# Swig2.net
KiCad netlist of a schematic drawn in EAGLE
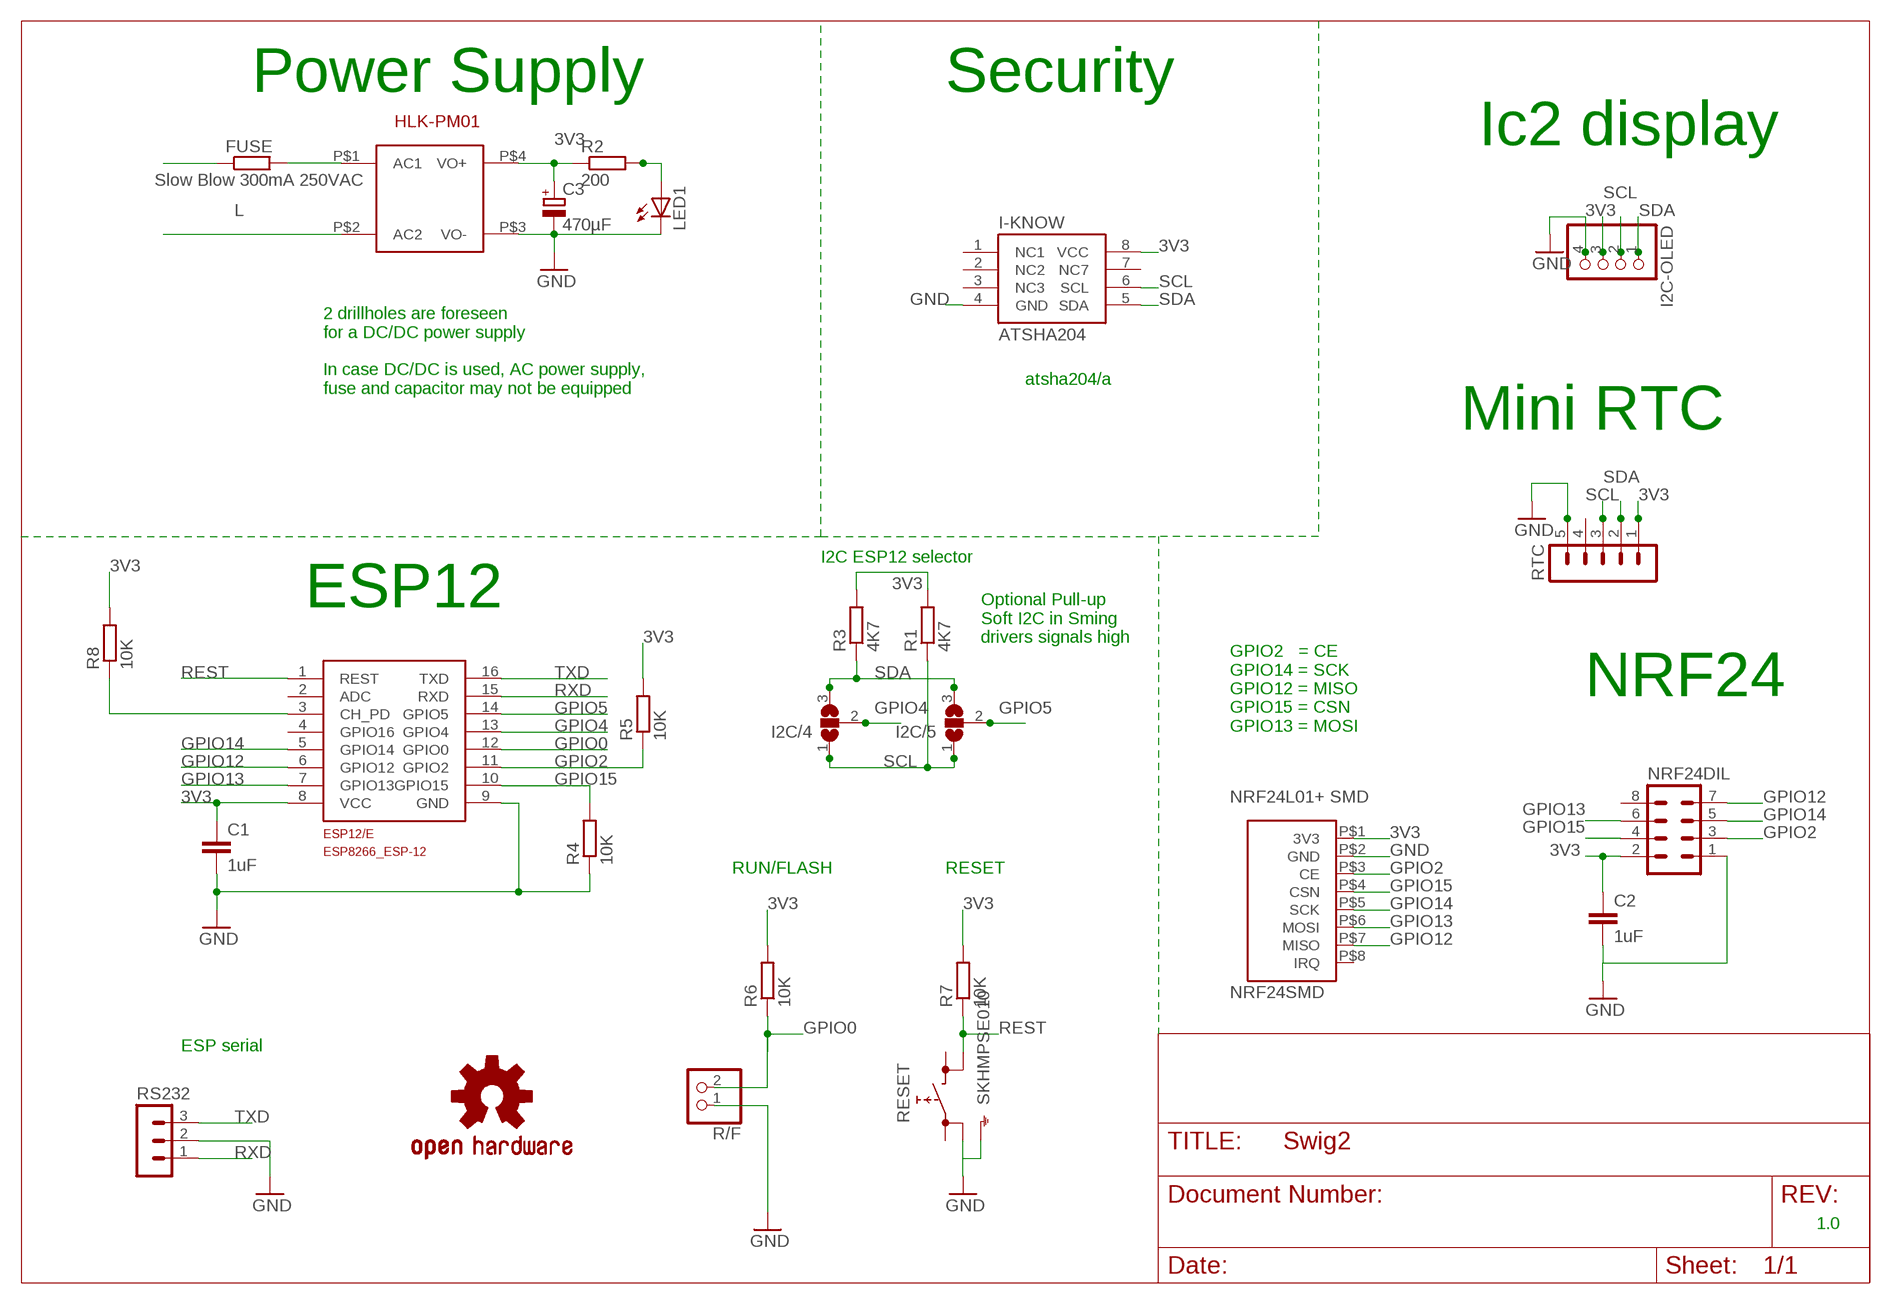
[diagram p0: schematic, sheet 1]

(export (version "E")
  (design (tool "Eeschema 10.0.6"))
  (components
    (comp (ref "C1")
      (value "1uF")
      (footprint "eagle-import:C0805")
      (libsource (lib "eagle-import") (part "C-EUC0805"))
    )
    (comp (ref "C2")
      (value "1uF")
      (footprint "eagle-import:C0805")
      (libsource (lib "eagle-import") (part "C-EUC0805"))
    )
    (comp (ref "C3")
      (value "470µF")
      (footprint "eagle-import:E5-8,5")
      (libsource (lib "eagle-import") (part "CPOL-EUE5-8.5"))
    )
    (comp (ref "ESP12/E")
      (value "ESP8266-12GPIO04/05_CORRECTED")
      (footprint "eagle-import:ESP8266-ESP12")
      (libsource (lib "eagle-import") (part "ESP8266-12GPIO04/05_CORRECTED"))
    )
    (comp (ref "FUSE")
      (value "Slow Blow 300mA 250VAC")
      (footprint "eagle-import:0411V")
      (libsource (lib "eagle-import") (part "R-EU_0411/3V"))
    )
    (comp (ref "HLK-PM01")
      (value "HLK-PM01")
      (footprint "eagle-import:HLK-PM01")
      (libsource (lib "eagle-import") (part "HLK-PM01"))
    )
    (comp (ref "I-KNOW")
      (value "ATSHA204")
      (footprint "eagle-import:SOIC8")
      (libsource (lib "eagle-import") (part "ATSHA204"))
    )
    (comp (ref "I2C-OLED")
      (value "PINHD-1X4")
      (footprint "eagle-import:1X04")
      (libsource (lib "eagle-import") (part "PINHD-1X4"))
    )
    (comp (ref "I2C/4")
      (value "SJ2W")
      (footprint "eagle-import:SJ_2")
      (libsource (lib "eagle-import") (part "SJ2W"))
    )
    (comp (ref "I2C/5")
      (value "SJ2W")
      (footprint "eagle-import:SJ_2")
      (libsource (lib "eagle-import") (part "SJ2W"))
    )
    (comp (ref "LED1")
      (value "LED5MM")
      (footprint "eagle-import:LED5MM")
      (libsource (lib "eagle-import") (part "LED5MM"))
    )
    (comp (ref "LOGO2")
      (value "OSHW-LOGOS")
      (footprint "eagle-import:OSHW-LOGO-S")
      (libsource (lib "eagle-import") (part "OSHW-LOGOS"))
    )
    (comp (ref "NRF24DIL")
      (value "MA04-2")
      (footprint "eagle-import:MA04-2")
      (libsource (lib "eagle-import") (part "MA04-2"))
    )
    (comp (ref "NRF24SMD")
      (value "NRF24L01+SMD")
      (footprint "eagle-import:NRF24L01+SMD")
      (libsource (lib "eagle-import") (part "NRF24L01+SMD"))
    )
    (comp (ref "R/F")
      (value "PINHD-1X2")
      (footprint "eagle-import:1X02")
      (libsource (lib "eagle-import") (part "PINHD-1X2"))
    )
    (comp (ref "R1")
      (value "4K7")
      (footprint "eagle-import:R0805")
      (libsource (lib "eagle-import") (part "resistor_R-EU_R0805"))
    )
    (comp (ref "R2")
      (value "200")
      (footprint "eagle-import:R0805")
      (libsource (lib "eagle-import") (part "R-EU_R0805"))
    )
    (comp (ref "R3")
      (value "4K7")
      (footprint "eagle-import:R0805")
      (libsource (lib "eagle-import") (part "resistor_R-EU_R0805"))
    )
    (comp (ref "R4")
      (value "10K")
      (footprint "eagle-import:R0805")
      (libsource (lib "eagle-import") (part "resistor_R-EU_R0805"))
    )
    (comp (ref "R5")
      (value "10K")
      (footprint "eagle-import:R0805")
      (libsource (lib "eagle-import") (part "resistor_R-EU_R0805"))
    )
    (comp (ref "R6")
      (value "10K")
      (footprint "eagle-import:R0805")
      (libsource (lib "eagle-import") (part "resistor_R-EU_R0805"))
    )
    (comp (ref "R7")
      (value "10K")
      (footprint "eagle-import:R0805")
      (libsource (lib "eagle-import") (part "resistor_R-EU_R0805"))
    )
    (comp (ref "R8")
      (value "10K")
      (footprint "eagle-import:R0805")
      (libsource (lib "eagle-import") (part "resistor_R-EU_R0805"))
    )
    (comp (ref "RESET")
      (value "SKHMPSE010")
      (footprint "eagle-import:SKHMPXE010")
      (libsource (lib "eagle-import") (part "SKHMPE010S"))
    )
    (comp (ref "RS232")
      (value "MA03-1")
      (footprint "eagle-import:MA03-1")
      (libsource (lib "eagle-import") (part "MA03-1"))
    )
    (comp (ref "RTC")
      (value "MA05-1")
      (footprint "eagle-import:MA05-1")
      (libsource (lib "eagle-import") (part "MA05-1"))
    )
  )
  (nets
    (net (code "1") (name "/3V3") (class "Default")
      (node (ref "C1") (pin "1") (pinfunction "1_1") (pintype "passive"))
      (node (ref "C2") (pin "1") (pinfunction "1_1") (pintype "passive"))
      (node (ref "C3") (pin "+") (pinfunction "+_+") (pintype "passive"))
      (node (ref "ESP12/E") (pin "8") (pinfunction "VCC_8") (pintype "bidirectional"))
      (node (ref "HLK-PM01") (pin "P$4") (pinfunction "VO+_P$4") (pintype "power_in"))
      (node (ref "I-KNOW") (pin "8") (pinfunction "VCC_8") (pintype "power_in"))
      (node (ref "I2C-OLED") (pin "3") (pinfunction "3_3") (pintype "passive"))
      (node (ref "NRF24DIL") (pin "2") (pinfunction "2_2") (pintype "passive"))
      (node (ref "NRF24SMD") (pin "P$1") (pinfunction "3V3_P$1") (pintype "bidirectional"))
      (node (ref "R1") (pin "2") (pinfunction "2_2") (pintype "passive"))
      (node (ref "R2") (pin "1") (pinfunction "1_1") (pintype "passive"))
      (node (ref "R3") (pin "2") (pinfunction "2_2") (pintype "passive"))
      (node (ref "R5") (pin "2") (pinfunction "2_2") (pintype "passive"))
      (node (ref "R6") (pin "2") (pinfunction "2_2") (pintype "passive"))
      (node (ref "R7") (pin "2") (pinfunction "2_2") (pintype "passive"))
      (node (ref "R8") (pin "2") (pinfunction "2_2") (pintype "passive"))
      (node (ref "RTC") (pin "1") (pinfunction "1_1") (pintype "passive"))
    )
    (net (code "2") (name "/GPIO0") (class "Default")
      (node (ref "ESP12/E") (pin "12") (pinfunction "GPIO0_12") (pintype "bidirectional"))
      (node (ref "R/F") (pin "2") (pinfunction "2_2") (pintype "passive"))
      (node (ref "R6") (pin "1") (pinfunction "1_1") (pintype "passive"))
    )
    (net (code "3") (name "/GPIO2") (class "Default")
      (node (ref "ESP12/E") (pin "11") (pinfunction "GPIO2_11") (pintype "bidirectional"))
      (node (ref "NRF24DIL") (pin "3") (pinfunction "3_3") (pintype "passive"))
      (node (ref "NRF24SMD") (pin "P$3") (pinfunction "CE_P$3") (pintype "bidirectional"))
      (node (ref "R5") (pin "1") (pinfunction "1_1") (pintype "passive"))
    )
    (net (code "4") (name "/GPIO4") (class "Default")
      (node (ref "ESP12/E") (pin "13") (pinfunction "GPIO4_13") (pintype "bidirectional"))
      (node (ref "I2C/4") (pin "2") (pinfunction "2_2") (pintype "passive"))
    )
    (net (code "5") (name "/GPIO5") (class "Default")
      (node (ref "ESP12/E") (pin "14") (pinfunction "GPIO5_14") (pintype "bidirectional"))
      (node (ref "I2C/5") (pin "2") (pinfunction "2_2") (pintype "passive"))
    )
    (net (code "6") (name "/GPIO12") (class "Default")
      (node (ref "ESP12/E") (pin "6") (pinfunction "GPIO12_6") (pintype "bidirectional"))
      (node (ref "NRF24DIL") (pin "7") (pinfunction "7_7") (pintype "passive"))
      (node (ref "NRF24SMD") (pin "P$7") (pinfunction "MISO_P$7") (pintype "bidirectional"))
    )
    (net (code "7") (name "/GPIO13") (class "Default")
      (node (ref "ESP12/E") (pin "7") (pinfunction "GPIO13_7") (pintype "bidirectional"))
      (node (ref "NRF24DIL") (pin "6") (pinfunction "6_6") (pintype "passive"))
      (node (ref "NRF24SMD") (pin "P$6") (pinfunction "MOSI_P$6") (pintype "bidirectional"))
    )
    (net (code "8") (name "/GPIO14") (class "Default")
      (node (ref "ESP12/E") (pin "5") (pinfunction "GPIO14_5") (pintype "bidirectional"))
      (node (ref "NRF24DIL") (pin "5") (pinfunction "5_5") (pintype "passive"))
      (node (ref "NRF24SMD") (pin "P$5") (pinfunction "SCK_P$5") (pintype "bidirectional"))
    )
    (net (code "9") (name "/GPIO15") (class "Default")
      (node (ref "ESP12/E") (pin "10") (pinfunction "GPIO15_10") (pintype "bidirectional"))
      (node (ref "NRF24DIL") (pin "4") (pinfunction "4_4") (pintype "passive"))
      (node (ref "NRF24SMD") (pin "P$4") (pinfunction "CSN_P$4") (pintype "bidirectional"))
      (node (ref "R4") (pin "2") (pinfunction "2_2") (pintype "passive"))
    )
    (net (code "10") (name "/L") (class "Default")
      (node (ref "HLK-PM01") (pin "P$2") (pinfunction "AC2_P$2") (pintype "input"))
    )
    (net (code "11") (name "/REST") (class "Default")
      (node (ref "ESP12/E") (pin "1") (pinfunction "REST_1") (pintype "bidirectional"))
      (node (ref "R7") (pin "1") (pinfunction "1_1") (pintype "passive"))
      (node (ref "RESET") (pin "4") (pinfunction "2.2_4") (pintype "passive"))
    )
    (net (code "12") (name "/RXD") (class "Default")
      (node (ref "ESP12/E") (pin "15") (pinfunction "RXD_15") (pintype "bidirectional"))
      (node (ref "RS232") (pin "1") (pinfunction "1_1") (pintype "passive"))
    )
    (net (code "13") (name "/SCL") (class "Default")
      (node (ref "I-KNOW") (pin "6") (pinfunction "SCL_6") (pintype "bidirectional"))
      (node (ref "I2C-OLED") (pin "2") (pinfunction "2_2") (pintype "passive"))
      (node (ref "I2C/4") (pin "1") (pinfunction "1_1") (pintype "passive"))
      (node (ref "I2C/5") (pin "1") (pinfunction "1_1") (pintype "passive"))
      (node (ref "R1") (pin "1") (pinfunction "1_1") (pintype "passive"))
      (node (ref "RTC") (pin "3") (pinfunction "3_3") (pintype "passive"))
    )
    (net (code "14") (name "/SDA") (class "Default")
      (node (ref "I-KNOW") (pin "5") (pinfunction "SDA_5") (pintype "bidirectional"))
      (node (ref "I2C-OLED") (pin "1") (pinfunction "1_1") (pintype "passive"))
      (node (ref "I2C/4") (pin "3") (pinfunction "3_3") (pintype "passive"))
      (node (ref "I2C/5") (pin "3") (pinfunction "3_3") (pintype "passive"))
      (node (ref "R3") (pin "1") (pinfunction "1_1") (pintype "passive"))
      (node (ref "RTC") (pin "2") (pinfunction "2_2") (pintype "passive"))
    )
    (net (code "15") (name "/TXD") (class "Default")
      (node (ref "ESP12/E") (pin "16") (pinfunction "TXD_16") (pintype "bidirectional"))
      (node (ref "RS232") (pin "3") (pinfunction "3_3") (pintype "passive"))
    )
    (net (code "16") (name "GND") (class "Default")
      (node (ref "C1") (pin "2") (pinfunction "2_2") (pintype "passive"))
      (node (ref "C2") (pin "2") (pinfunction "2_2") (pintype "passive"))
      (node (ref "C3") (pin "-") (pinfunction "-_-") (pintype "passive"))
      (node (ref "ESP12/E") (pin "9") (pinfunction "GND_9") (pintype "bidirectional"))
      (node (ref "HLK-PM01") (pin "P$3") (pinfunction "VO-_P$3") (pintype "power_in"))
      (node (ref "I-KNOW") (pin "4") (pinfunction "GND_4") (pintype "power_in"))
      (node (ref "I2C-OLED") (pin "4") (pinfunction "4_4") (pintype "passive"))
      (node (ref "LED1") (pin "K") (pinfunction "C_K") (pintype "passive"))
      (node (ref "NRF24DIL") (pin "1") (pinfunction "1_1") (pintype "passive"))
      (node (ref "NRF24SMD") (pin "P$2") (pinfunction "GND_P$2") (pintype "bidirectional"))
      (node (ref "R/F") (pin "1") (pinfunction "1_1") (pintype "passive"))
      (node (ref "R4") (pin "1") (pinfunction "1_1") (pintype "passive"))
      (node (ref "RESET") (pin "2") (pinfunction "1.2_2") (pintype "passive"))
      (node (ref "RESET") (pin "5") (pinfunction "SH_5") (pintype "passive"))
      (node (ref "RS232") (pin "2") (pinfunction "2_2") (pintype "passive"))
      (node (ref "RTC") (pin "5") (pinfunction "5_5") (pintype "passive"))
    )
    (net (code "17") (name "Net-(ESP12/E-CH_PD)") (class "Default")
      (node (ref "ESP12/E") (pin "3") (pinfunction "CH_PD_3") (pintype "bidirectional"))
      (node (ref "R8") (pin "1") (pinfunction "1_1") (pintype "passive"))
    )
    (net (code "18") (name "Net-(HLK-PM01-AC1)") (class "Default")
      (node (ref "FUSE") (pin "2") (pinfunction "2_2") (pintype "passive"))
      (node (ref "HLK-PM01") (pin "P$1") (pinfunction "AC1_P$1") (pintype "input"))
    )
    (net (code "19") (name "Net-(LED1-PadA)") (class "Default")
      (node (ref "LED1") (pin "A") (pinfunction "A_A") (pintype "passive"))
      (node (ref "R2") (pin "2") (pinfunction "2_2") (pintype "passive"))
    )
    (net (code "20") (name "unconnected-(ESP12/E-ADC-Pad2)") (class "Default")
      (node (ref "ESP12/E") (pin "2") (pinfunction "ADC_2") (pintype "bidirectional"))
    )
    (net (code "21") (name "unconnected-(ESP12/E-GPIO16-Pad4)") (class "Default")
      (node (ref "ESP12/E") (pin "4") (pinfunction "GPIO16_4") (pintype "bidirectional"))
    )
    (net (code "22") (name "unconnected-(FUSE-Pad1)") (class "Default")
      (node (ref "FUSE") (pin "1") (pinfunction "1_1") (pintype "passive"))
    )
    (net (code "23") (name "unconnected-(I-KNOW-NC1-Pad1)") (class "Default")
      (node (ref "I-KNOW") (pin "1") (pinfunction "NC1_1") (pintype "no_connect"))
    )
    (net (code "24") (name "unconnected-(I-KNOW-NC2-Pad2)") (class "Default")
      (node (ref "I-KNOW") (pin "2") (pinfunction "NC2_2") (pintype "no_connect"))
    )
    (net (code "25") (name "unconnected-(I-KNOW-NC3-Pad3)") (class "Default")
      (node (ref "I-KNOW") (pin "3") (pinfunction "NC3_3") (pintype "no_connect"))
    )
    (net (code "26") (name "unconnected-(I-KNOW-NC7-Pad7)") (class "Default")
      (node (ref "I-KNOW") (pin "7") (pinfunction "NC7_7") (pintype "no_connect"))
    )
    (net (code "27") (name "unconnected-(NRF24DIL-Pad8)") (class "Default")
      (node (ref "NRF24DIL") (pin "8") (pinfunction "8_8") (pintype "passive"))
    )
    (net (code "28") (name "unconnected-(NRF24SMD-IRQ-PadP$8)") (class "Default")
      (node (ref "NRF24SMD") (pin "P$8") (pinfunction "IRQ_P$8") (pintype "bidirectional"))
    )
    (net (code "29") (name "unconnected-(RESET-1.1-Pad1)") (class "Default")
      (node (ref "RESET") (pin "1") (pinfunction "1.1_1") (pintype "passive"))
    )
    (net (code "30") (name "unconnected-(RESET-2.1-Pad3)") (class "Default")
      (node (ref "RESET") (pin "3") (pinfunction "2.1_3") (pintype "passive"))
    )
    (net (code "31") (name "unconnected-(RTC-Pad4)") (class "Default")
      (node (ref "RTC") (pin "4") (pinfunction "4_4") (pintype "passive"))
    )
  )
)
